# ControlPCB_2025-04-28.net
KiCad netlist of a schematic drawn in EAGLE
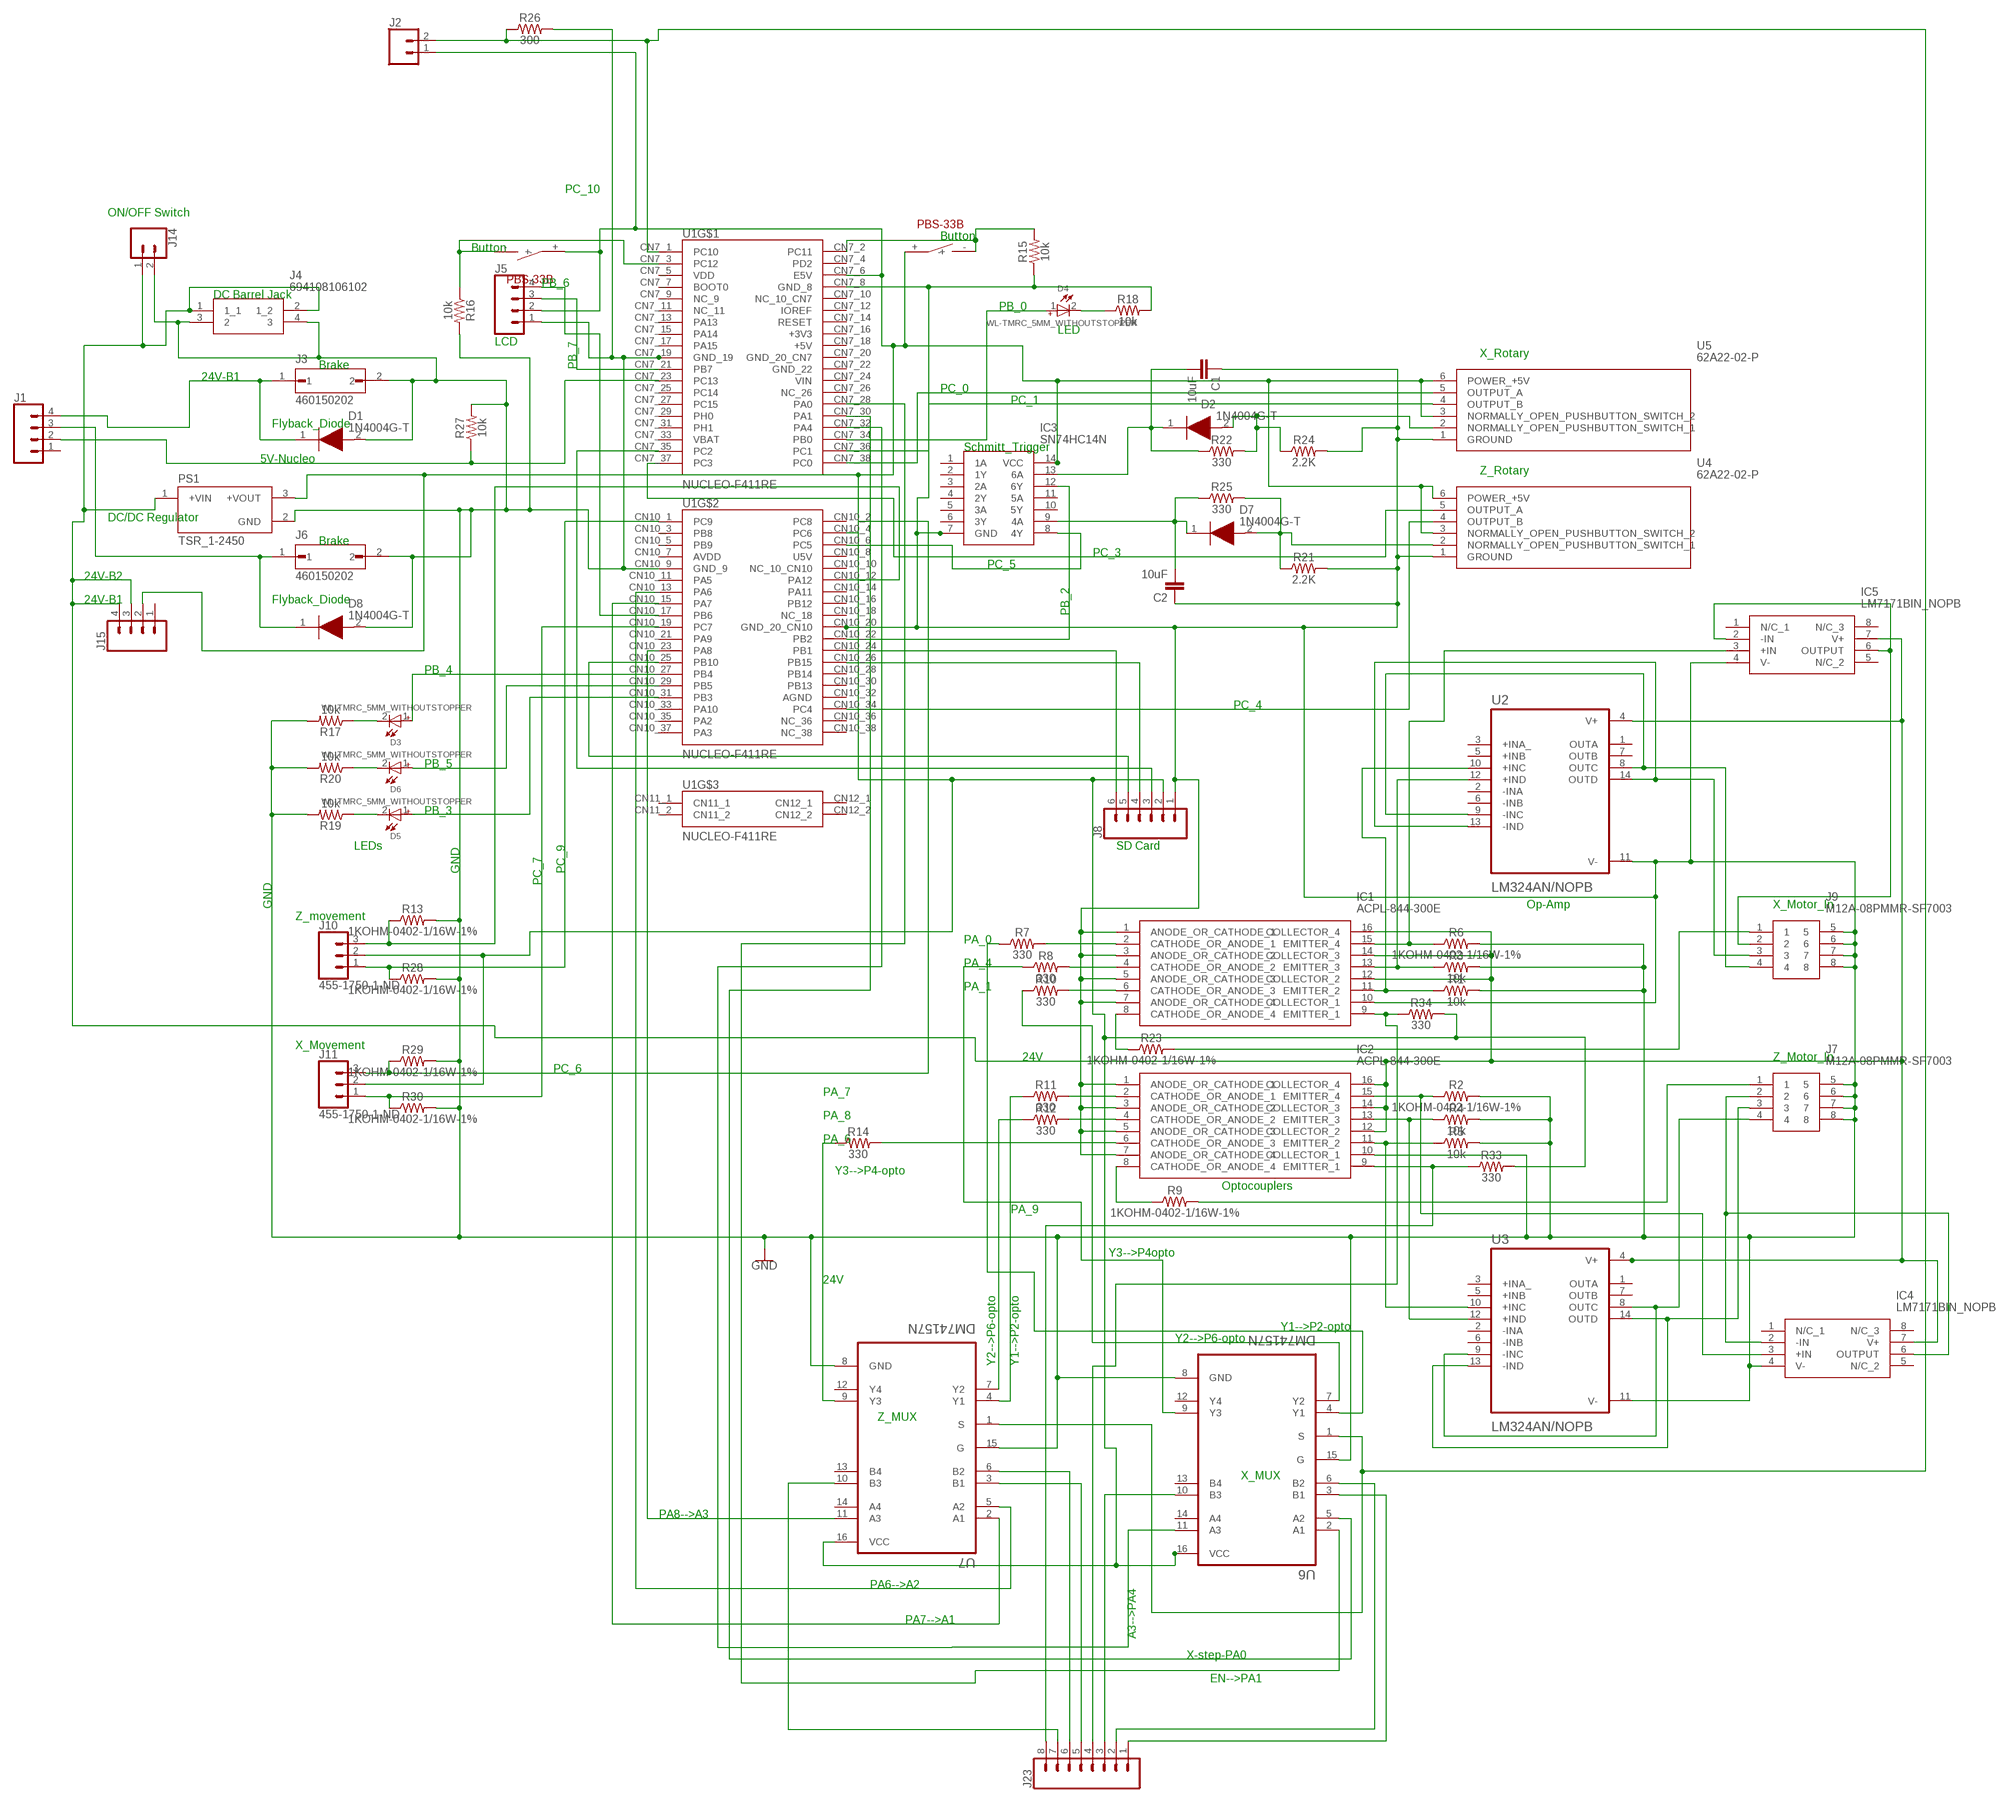
[diagram p0: schematic, sheet 1]

(export (version "E")
  (design (tool "Eeschema 10.0.6"))
  (components
    (comp (ref "C1")
      (value "10uF")
      (footprint "eagle-import:0603")
      (libsource (lib "eagle-import") (part "10UF-0603-6.3V-20%"))
    )
    (comp (ref "C2")
      (value "10uF")
      (footprint "eagle-import:0603")
      (libsource (lib "eagle-import") (part "10UF-0603-6.3V-20%"))
    )
    (comp (ref "D1")
      (value "1N4004G-T")
      (footprint "eagle-import:DIOAD1408W86L464D236")
      (fields (field (name "MOUSER_PART_NUMBER") "621-1N4004G-T"))
      (libsource (lib "eagle-import") (part "1N4004G-T"))
    )
    (comp (ref "D2")
      (value "1N4004G-T")
      (footprint "eagle-import:DIOAD1408W86L464D236")
      (fields (field (name "MOUSER_PART_NUMBER") "621-1N4004G-T"))
      (libsource (lib "eagle-import") (part "1N4004G-T"))
    )
    (comp (ref "D3")
      (value "WL-TMRC_5MM_WITHOUTSTOPPER")
      (footprint "eagle-import:WL-TMRC_5MM")
      (libsource (lib "eagle-import") (part "WL-TMRC_5MM_WITHOUTSTOPPER"))
    )
    (comp (ref "D4")
      (value "WL-TMRC_5MM_WITHOUTSTOPPER")
      (footprint "eagle-import:WL-TMRC_5MM")
      (libsource (lib "eagle-import") (part "WL-TMRC_5MM_WITHOUTSTOPPER"))
    )
    (comp (ref "D5")
      (value "WL-TMRC_5MM_WITHOUTSTOPPER")
      (footprint "eagle-import:WL-TMRC_5MM")
      (libsource (lib "eagle-import") (part "WL-TMRC_5MM_WITHOUTSTOPPER"))
    )
    (comp (ref "D6")
      (value "WL-TMRC_5MM_WITHOUTSTOPPER")
      (footprint "eagle-import:WL-TMRC_5MM")
      (libsource (lib "eagle-import") (part "WL-TMRC_5MM_WITHOUTSTOPPER"))
    )
    (comp (ref "D7")
      (value "1N4004G-T")
      (footprint "eagle-import:DIOAD1408W86L464D236")
      (fields (field (name "MOUSER_PART_NUMBER") "621-1N4004G-T"))
      (libsource (lib "eagle-import") (part "1N4004G-T"))
    )
    (comp (ref "D8")
      (value "1N4004G-T")
      (footprint "eagle-import:DIOAD1408W86L464D236")
      (fields (field (name "MOUSER_PART_NUMBER") "621-1N4004G-T"))
      (libsource (lib "eagle-import") (part "1N4004G-T"))
    )
    (comp (ref "IC1")
      (value "ACPL-844-300E")
      (footprint "eagle-import:DIP880W60P254L1984H450Q16N")
      (fields (field (name "MOUSER_PART_NUMBER") "630-ACPL-844-300E"))
      (libsource (lib "eagle-import") (part "ACPL-844-300E"))
    )
    (comp (ref "IC2")
      (value "ACPL-844-300E")
      (footprint "eagle-import:DIP880W60P254L1984H450Q16N")
      (fields (field (name "MOUSER_PART_NUMBER") "630-ACPL-844-300E"))
      (libsource (lib "eagle-import") (part "ACPL-844-300E"))
    )
    (comp (ref "IC3")
      (value "SN74HC14N")
      (footprint "eagle-import:DIP794W53P254L1930H508Q14N")
      (fields (field (name "MOUSER_PART_NUMBER") "595-SN74HC14N"))
      (libsource (lib "eagle-import") (part "SN74HC14N"))
    )
    (comp (ref "IC4")
      (value "LM7171BIN_NOPB")
      (footprint "eagle-import:DIP794W53P254L959H508Q8N")
      (fields
        (field (name "ARROW_PART_NUMBER") "LM7171BIN/NOPB")
        (field (name "MOUSER_PART_NUMBER") "926-LM7171BIN/NOPB")
      )
      (libsource (lib "eagle-import") (part "LM7171BIN_NOPB"))
    )
    (comp (ref "IC5")
      (value "LM7171BIN_NOPB")
      (footprint "eagle-import:DIP794W53P254L959H508Q8N")
      (fields
        (field (name "ARROW_PART_NUMBER") "LM7171BIN/NOPB")
        (field (name "MOUSER_PART_NUMBER") "926-LM7171BIN/NOPB")
      )
      (libsource (lib "eagle-import") (part "LM7171BIN_NOPB"))
    )
    (comp (ref "J1")
      (value "CONN_04PTH")
      (footprint "eagle-import:1X04")
      (libsource (lib "eagle-import") (part "CONN_04PTH"))
    )
    (comp (ref "J2")
      (value "CONN_02")
      (footprint "eagle-import:1X02")
      (libsource (lib "eagle-import") (part "CONN_02"))
    )
    (comp (ref "J3")
      (value "460150202")
      (footprint "eagle-import:MOLEX_460150202")
      (fields (field (name "MANUFACTURER") "Molex"))
      (libsource (lib "eagle-import") (part "460150202"))
    )
    (comp (ref "J4")
      (value "694108106102")
      (footprint "eagle-import:694108106102")
      (fields (field (name "MOUSER_PART_NUMBER") "710-694108106102"))
      (libsource (lib "eagle-import") (part "694108106102"))
    )
    (comp (ref "J5")
      (value "CONN_04LOCK")
      (footprint "eagle-import:1X04_LOCK")
      (libsource (lib "eagle-import") (part "CONN_04LOCK"))
    )
    (comp (ref "J6")
      (value "460150202")
      (footprint "eagle-import:MOLEX_460150202")
      (fields (field (name "MANUFACTURER") "Molex"))
      (libsource (lib "eagle-import") (part "460150202"))
    )
    (comp (ref "J7")
      (value "M12A-08PMMR-SF7003")
      (footprint "eagle-import:M12A08PMMRSF7003")
      (fields (field (name "MOUSER_PART_NUMBER") "523-M12A08PMMRSF7003"))
      (libsource (lib "eagle-import") (part "M12A-08PMMR-SF7003"))
    )
    (comp (ref "J8")
      (value "CONN_06SILK_FEMALE_PTH")
      (footprint "eagle-import:1X06")
      (libsource (lib "eagle-import") (part "CONN_06SILK_FEMALE_PTH"))
    )
    (comp (ref "J9")
      (value "M12A-08PMMR-SF7003")
      (footprint "eagle-import:M12A08PMMRSF7003")
      (fields (field (name "MOUSER_PART_NUMBER") "523-M12A08PMMRSF7003"))
      (libsource (lib "eagle-import") (part "M12A-08PMMR-SF7003"))
    )
    (comp (ref "J10")
      (value "455-1750-1-ND")
      (footprint "eagle-import:1X03")
      (libsource (lib "eagle-import") (part "CONN_03"))
    )
    (comp (ref "J11")
      (value "455-1750-1-ND")
      (footprint "eagle-import:1X03")
      (libsource (lib "eagle-import") (part "CONN_03"))
    )
    (comp (ref "J14")
      (value "CONN_02")
      (footprint "eagle-import:1X02")
      (libsource (lib "eagle-import") (part "CONN_02"))
    )
    (comp (ref "J15")
      (value "CONN_04PTH")
      (footprint "eagle-import:1X04")
      (libsource (lib "eagle-import") (part "CONN_04PTH"))
    )
    (comp (ref "J23")
      (value "CONN_08\"")
      (footprint "eagle-import:1X08")
      (libsource (lib "eagle-import") (part "CONN_08{dblquote}"))
    )
    (comp (ref "PS1")
      (value "TSR_1-2450")
      (footprint "eagle-import:CONV_TSR_1-2450")
      (fields (field (name "MANUFACTURER") "Traco Power"))
      (libsource (lib "eagle-import") (part "TSR_1-2450"))
    )
    (comp (ref "R1")
      (value "10k")
      (footprint "eagle-import:0402")
      (libsource (lib "eagle-import") (part "10KOHM-0402-1/16W-1%"))
    )
    (comp (ref "R2")
      (value "1KOHM-0402-1/16W-1%")
      (footprint "eagle-import:0402")
      (libsource (lib "eagle-import") (part "1KOHM-0402-1/16W-1%"))
    )
    (comp (ref "R3")
      (value "10k")
      (footprint "eagle-import:0402")
      (libsource (lib "eagle-import") (part "10KOHM-0402-1/16W-1%"))
    )
    (comp (ref "R4")
      (value "10k")
      (footprint "eagle-import:0402")
      (libsource (lib "eagle-import") (part "10KOHM-0402-1/16W-1%"))
    )
    (comp (ref "R5")
      (value "10k")
      (footprint "eagle-import:0402")
      (libsource (lib "eagle-import") (part "10KOHM-0402-1/16W-1%"))
    )
    (comp (ref "R6")
      (value "1KOHM-0402-1/16W-1%")
      (footprint "eagle-import:0402")
      (libsource (lib "eagle-import") (part "1KOHM-0402-1/16W-1%"))
    )
    (comp (ref "R7")
      (value "330")
      (footprint "eagle-import:0402")
      (libsource (lib "eagle-import") (part "330OHM-0402-1/16W-5%"))
    )
    (comp (ref "R8")
      (value "330")
      (footprint "eagle-import:0402")
      (libsource (lib "eagle-import") (part "330OHM-0402-1/16W-5%"))
    )
    (comp (ref "R9")
      (value "1KOHM-0402-1/16W-1%")
      (footprint "eagle-import:0402")
      (libsource (lib "eagle-import") (part "1KOHM-0402-1/16W-1%"))
    )
    (comp (ref "R10")
      (value "330")
      (footprint "eagle-import:0402")
      (libsource (lib "eagle-import") (part "330OHM-0402-1/16W-5%"))
    )
    (comp (ref "R11")
      (value "330")
      (footprint "eagle-import:0402")
      (libsource (lib "eagle-import") (part "330OHM-0402-1/16W-5%"))
    )
    (comp (ref "R12")
      (value "330")
      (footprint "eagle-import:0402")
      (libsource (lib "eagle-import") (part "330OHM-0402-1/16W-5%"))
    )
    (comp (ref "R13")
      (value "1KOHM-0402-1/16W-1%")
      (footprint "eagle-import:0402")
      (libsource (lib "eagle-import") (part "1KOHM-0402-1/16W-1%"))
    )
    (comp (ref "R14")
      (value "330")
      (footprint "eagle-import:0402")
      (libsource (lib "eagle-import") (part "330OHM-0402-1/16W-5%"))
    )
    (comp (ref "R15")
      (value "10k")
      (footprint "eagle-import:0402")
      (libsource (lib "eagle-import") (part "10KOHM-0402-1/16W-1%"))
    )
    (comp (ref "R16")
      (value "10k")
      (footprint "eagle-import:0402")
      (libsource (lib "eagle-import") (part "10KOHM-0402-1/16W-1%"))
    )
    (comp (ref "R17")
      (value "10k")
      (footprint "eagle-import:0402")
      (libsource (lib "eagle-import") (part "10KOHM-0402-1/16W-1%"))
    )
    (comp (ref "R18")
      (value "10k")
      (footprint "eagle-import:0402")
      (libsource (lib "eagle-import") (part "10KOHM-0402-1/16W-1%"))
    )
    (comp (ref "R19")
      (value "10k")
      (footprint "eagle-import:0402")
      (libsource (lib "eagle-import") (part "10KOHM-0402-1/16W-1%"))
    )
    (comp (ref "R20")
      (value "10k")
      (footprint "eagle-import:0402")
      (libsource (lib "eagle-import") (part "10KOHM-0402-1/16W-1%"))
    )
    (comp (ref "R21")
      (value "2.2K")
      (footprint "eagle-import:0402")
      (libsource (lib "eagle-import") (part "2.2KOHM-0402-1/16W-1%"))
    )
    (comp (ref "R22")
      (value "330")
      (footprint "eagle-import:0402")
      (libsource (lib "eagle-import") (part "330OHM-0402-1/16W-5%"))
    )
    (comp (ref "R23")
      (value "1KOHM-0402-1/16W-1%")
      (footprint "eagle-import:0402")
      (libsource (lib "eagle-import") (part "1KOHM-0402-1/16W-1%"))
    )
    (comp (ref "R24")
      (value "2.2K")
      (footprint "eagle-import:0402")
      (libsource (lib "eagle-import") (part "2.2KOHM-0402-1/16W-1%"))
    )
    (comp (ref "R25")
      (value "330")
      (footprint "eagle-import:0402")
      (libsource (lib "eagle-import") (part "330OHM-0402-1/16W-5%"))
    )
    (comp (ref "R26")
      (value "300")
      (footprint "eagle-import:0603")
      (libsource (lib "eagle-import") (part "300OHM-0603-1/10W-1%"))
    )
    (comp (ref "R27")
      (value "10k")
      (footprint "eagle-import:0402")
      (libsource (lib "eagle-import") (part "10KOHM-0402-1/16W-1%"))
    )
    (comp (ref "R28")
      (value "1KOHM-0402-1/16W-1%")
      (footprint "eagle-import:0402")
      (libsource (lib "eagle-import") (part "1KOHM-0402-1/16W-1%"))
    )
    (comp (ref "R29")
      (value "1KOHM-0402-1/16W-1%")
      (footprint "eagle-import:0402")
      (libsource (lib "eagle-import") (part "1KOHM-0402-1/16W-1%"))
    )
    (comp (ref "R30")
      (value "1KOHM-0402-1/16W-1%")
      (footprint "eagle-import:0402")
      (libsource (lib "eagle-import") (part "1KOHM-0402-1/16W-1%"))
    )
    (comp (ref "R33")
      (value "330")
      (footprint "eagle-import:0402")
      (libsource (lib "eagle-import") (part "330OHM-0402-1/16W-5%"))
    )
    (comp (ref "R34")
      (value "330")
      (footprint "eagle-import:0402")
      (libsource (lib "eagle-import") (part "330OHM-0402-1/16W-5%"))
    )
    (comp (ref "U$1")
      (value "PBS-33B")
      (footprint "eagle-import:PBS-33B")
      (libsource (lib "eagle-import") (part "PBS-33B"))
    )
    (comp (ref "U$2")
      (value "PBS-33B")
      (footprint "eagle-import:PBS-33B")
      (libsource (lib "eagle-import") (part "PBS-33B"))
    )
    (comp (ref "U1")
      (value "NUCLEO-F411RE")
      (footprint "eagle-import:BOARD_NUCLEO-F411RE")
      (fields (field (name "DIGIKEY_PART_NUMBER") "497-14711-ND") (field (name "MF") "STMicroelectronics"))
      (libsource (lib "eagle-import") (part "NUCLEO-F411RE"))
    )
    (comp (ref "U2")
      (value "LM324AN/NOPB")
      (footprint "eagle-import:DIP794W45P254L1969H508Q14")
      (libsource (lib "eagle-import") (part "LM324AN/NOPB"))
    )
    (comp (ref "U3")
      (value "LM324AN/NOPB")
      (footprint "eagle-import:DIP794W45P254L1969H508Q14")
      (libsource (lib "eagle-import") (part "LM324AN/NOPB"))
    )
    (comp (ref "U4")
      (value "62A22-02-P")
      (footprint "eagle-import:62A2202P")
      (fields (field (name "MOUSER_PART_NUMBER") "706-62A22-02-P"))
      (libsource (lib "eagle-import") (part "62A22-02-P"))
    )
    (comp (ref "U5")
      (value "62A22-02-P")
      (footprint "eagle-import:62A2202P")
      (fields (field (name "MOUSER_PART_NUMBER") "706-62A22-02-P"))
      (libsource (lib "eagle-import") (part "62A22-02-P"))
    )
    (comp (ref "U6")
      (value "DM74157N")
      (footprint "eagle-import:DIP794W45P254L1918H533Q16")
      (fields (field (name "MF") "ON Semiconductor"))
      (libsource (lib "eagle-import") (part "DM74157N"))
    )
    (comp (ref "U7")
      (value "DM74157N")
      (footprint "eagle-import:DIP794W45P254L1918H533Q16")
      (fields (field (name "MF") "ON Semiconductor"))
      (libsource (lib "eagle-import") (part "DM74157N"))
    )
  )
  (nets
    (net (code "1") (name "/+3V3") (class "Default")
      (node (ref "U1") (pin "CN7_16") (pinfunction "+3V3_CN7_16") (pintype "power_in"))
    )
    (net (code "2") (name "/+5V") (class "Default")
      (node (ref "U1") (pin "CN7_18") (pinfunction "+5V_CN7_18") (pintype "power_in"))
    )
    (net (code "3") (name "/AGND") (class "Default")
      (node (ref "U1") (pin "CN10_32") (pinfunction "AGND_CN10_32") (pintype "power_in"))
    )
    (net (code "4") (name "/AVDD") (class "Default")
      (node (ref "U1") (pin "CN10_7") (pinfunction "AVDD_CN10_7") (pintype "power_in"))
    )
    (net (code "5") (name "/GND_20_CN7") (class "Default")
      (node (ref "U1") (pin "CN7_20") (pinfunction "GND_20_CN7_CN7_20") (pintype "power_in"))
    )
    (net (code "6") (name "/GND_22") (class "Default")
      (node (ref "U1") (pin "CN7_22") (pinfunction "GND_22_CN7_22") (pintype "power_in"))
    )
    (net (code "7") (name "/U5V") (class "Default")
      (node (ref "U1") (pin "CN10_8") (pinfunction "U5V_CN10_8") (pintype "power_in"))
    )
    (net (code "8") (name "/VBAT") (class "Default")
      (node (ref "U1") (pin "CN7_33") (pinfunction "VBAT_CN7_33") (pintype "power_in"))
    )
    (net (code "9") (name "/VDD") (class "Default")
      (node (ref "U1") (pin "CN7_5") (pinfunction "VDD_CN7_5") (pintype "power_in"))
    )
    (net (code "10") (name "GND") (class "Default")
      (node (ref "C1") (pin "1") (pinfunction "1_1") (pintype "passive"))
      (node (ref "C2") (pin "1") (pinfunction "1_1") (pintype "passive"))
      (node (ref "D1") (pin "2") (pinfunction "A_2") (pintype "bidirectional"))
      (node (ref "D8") (pin "2") (pinfunction "A_2") (pintype "bidirectional"))
      (node (ref "IC1") (pin "1") (pinfunction "ANODE_OR_CATHODE_1_1") (pintype "bidirectional"))
      (node (ref "IC1") (pin "10") (pinfunction "COLLECTOR_1_10") (pintype "bidirectional"))
      (node (ref "IC1") (pin "3") (pinfunction "ANODE_OR_CATHODE_2_3") (pintype "bidirectional"))
      (node (ref "IC1") (pin "5") (pinfunction "ANODE_OR_CATHODE_3_5") (pintype "bidirectional"))
      (node (ref "IC1") (pin "7") (pinfunction "ANODE_OR_CATHODE_4_7") (pintype "bidirectional"))
      (node (ref "IC2") (pin "1") (pinfunction "ANODE_OR_CATHODE_1_1") (pintype "bidirectional"))
      (node (ref "IC2") (pin "10") (pinfunction "COLLECTOR_1_10") (pintype "bidirectional"))
      (node (ref "IC2") (pin "3") (pinfunction "ANODE_OR_CATHODE_2_3") (pintype "bidirectional"))
      (node (ref "IC2") (pin "5") (pinfunction "ANODE_OR_CATHODE_3_5") (pintype "bidirectional"))
      (node (ref "IC2") (pin "7") (pinfunction "ANODE_OR_CATHODE_4_7") (pintype "bidirectional"))
      (node (ref "IC3") (pin "7") (pinfunction "GND_7") (pintype "bidirectional"))
      (node (ref "IC4") (pin "4") (pinfunction "V-_4") (pintype "bidirectional"))
      (node (ref "IC5") (pin "4") (pinfunction "V-_4") (pintype "bidirectional"))
      (node (ref "J14") (pin "2") (pinfunction "2_2") (pintype "passive"))
      (node (ref "J3") (pin "2") (pinfunction "2_2") (pintype "passive"))
      (node (ref "J4") (pin "3") (pinfunction "2_3") (pintype "bidirectional"))
      (node (ref "J4") (pin "4") (pinfunction "3_4") (pintype "bidirectional"))
      (node (ref "J5") (pin "1") (pinfunction "1_1") (pintype "passive"))
      (node (ref "J6") (pin "2") (pinfunction "2_2") (pintype "passive"))
      (node (ref "J7") (pin "5") (pinfunction "5_5") (pintype "bidirectional"))
      (node (ref "J7") (pin "6") (pinfunction "6_6") (pintype "bidirectional"))
      (node (ref "J7") (pin "7") (pinfunction "7_7") (pintype "bidirectional"))
      (node (ref "J7") (pin "8") (pinfunction "8_8") (pintype "bidirectional"))
      (node (ref "J8") (pin "1") (pinfunction "1_1") (pintype "passive"))
      (node (ref "J9") (pin "5") (pinfunction "5_5") (pintype "bidirectional"))
      (node (ref "J9") (pin "6") (pinfunction "6_6") (pintype "bidirectional"))
      (node (ref "J9") (pin "7") (pinfunction "7_7") (pintype "bidirectional"))
      (node (ref "J9") (pin "8") (pinfunction "8_8") (pintype "bidirectional"))
      (node (ref "PS1") (pin "2") (pinfunction "GND_2") (pintype "power_in"))
      (node (ref "R1") (pin "2") (pinfunction "2_2") (pintype "passive"))
      (node (ref "R13") (pin "2") (pinfunction "2_2") (pintype "passive"))
      (node (ref "R15") (pin "1") (pinfunction "1_1") (pintype "passive"))
      (node (ref "R16") (pin "2") (pinfunction "2_2") (pintype "passive"))
      (node (ref "R17") (pin "2") (pinfunction "2_2") (pintype "passive"))
      (node (ref "R18") (pin "2") (pinfunction "2_2") (pintype "passive"))
      (node (ref "R19") (pin "2") (pinfunction "2_2") (pintype "passive"))
      (node (ref "R2") (pin "2") (pinfunction "2_2") (pintype "passive"))
      (node (ref "R20") (pin "2") (pinfunction "2_2") (pintype "passive"))
      (node (ref "R21") (pin "2") (pinfunction "2_2") (pintype "passive"))
      (node (ref "R24") (pin "2") (pinfunction "2_2") (pintype "passive"))
      (node (ref "R26") (pin "2") (pinfunction "2_2") (pintype "passive"))
      (node (ref "R27") (pin "2") (pinfunction "2_2") (pintype "passive"))
      (node (ref "R28") (pin "2") (pinfunction "2_2") (pintype "passive"))
      (node (ref "R29") (pin "2") (pinfunction "2_2") (pintype "passive"))
      (node (ref "R3") (pin "2") (pinfunction "2_2") (pintype "passive"))
      (node (ref "R30") (pin "2") (pinfunction "2_2") (pintype "passive"))
      (node (ref "R4") (pin "2") (pinfunction "2_2") (pintype "passive"))
      (node (ref "R5") (pin "2") (pinfunction "2_2") (pintype "passive"))
      (node (ref "R6") (pin "2") (pinfunction "2_2") (pintype "passive"))
      (node (ref "U1") (pin "CN10_20") (pinfunction "GND_20_CN10_CN10_20") (pintype "power_in"))
      (node (ref "U1") (pin "CN10_9") (pinfunction "GND_9_CN10_9") (pintype "power_in"))
      (node (ref "U1") (pin "CN7_19") (pinfunction "GND_19_CN7_19") (pintype "power_in"))
      (node (ref "U1") (pin "CN7_8") (pinfunction "GND_8_CN7_8") (pintype "power_in"))
      (node (ref "U2") (pin "11") (pinfunction "V-_11") (pintype "power_in"))
      (node (ref "U3") (pin "11") (pinfunction "V-_11") (pintype "power_in"))
      (node (ref "U4") (pin "1") (pinfunction "GROUND_1") (pintype "bidirectional"))
      (node (ref "U5") (pin "1") (pinfunction "GROUND_1") (pintype "bidirectional"))
      (node (ref "U6") (pin "15") (pinfunction "G_15") (pintype "bidirectional"))
      (node (ref "U6") (pin "8") (pinfunction "GND_8") (pintype "power_in"))
      (node (ref "U7") (pin "15") (pinfunction "G_15") (pintype "bidirectional"))
      (node (ref "U7") (pin "8") (pinfunction "GND_8") (pintype "power_in"))
    )
    (net (code "11") (name "Net-(D1-K)") (class "Default")
      (node (ref "D1") (pin "1") (pinfunction "K_1") (pintype "bidirectional"))
      (node (ref "J1") (pin "4") (pinfunction "4_4") (pintype "passive"))
      (node (ref "J3") (pin "1") (pinfunction "1_1") (pintype "passive"))
    )
    (net (code "12") (name "Net-(D2-A)") (class "Default")
      (node (ref "D2") (pin "2") (pinfunction "A_2") (pintype "bidirectional"))
      (node (ref "R22") (pin "2") (pinfunction "2_2") (pintype "passive"))
      (node (ref "R24") (pin "1") (pinfunction "1_1") (pintype "passive"))
      (node (ref "U5") (pin "2") (pinfunction "NORMALLY_OPEN_PUSHBUTTON_SWITCH_1_2") (pintype "bidirectional"))
    )
    (net (code "13") (name "Net-(D2-K)") (class "Default")
      (node (ref "C1") (pin "2") (pinfunction "2_2") (pintype "passive"))
      (node (ref "D2") (pin "1") (pinfunction "K_1") (pintype "bidirectional"))
      (node (ref "IC3") (pin "13") (pinfunction "6A_13") (pintype "bidirectional"))
      (node (ref "R22") (pin "1") (pinfunction "1_1") (pintype "passive"))
    )
    (net (code "14") (name "Net-(D3-+)") (class "Default")
      (node (ref "D3") (pin "1") (pinfunction "+_1") (pintype "passive"))
      (node (ref "U1") (pin "CN10_27") (pinfunction "PB4_CN10_27") (pintype "bidirectional"))
    )
    (net (code "15") (name "Net-(D3--)") (class "Default")
      (node (ref "D3") (pin "2") (pinfunction "-_2") (pintype "passive"))
      (node (ref "R17") (pin "1") (pinfunction "1_1") (pintype "passive"))
    )
    (net (code "16") (name "Net-(D4-+)") (class "Default")
      (node (ref "D4") (pin "1") (pinfunction "+_1") (pintype "passive"))
      (node (ref "U1") (pin "CN7_34") (pinfunction "PB0_CN7_34") (pintype "bidirectional"))
    )
    (net (code "17") (name "Net-(D4--)") (class "Default")
      (node (ref "D4") (pin "2") (pinfunction "-_2") (pintype "passive"))
      (node (ref "R18") (pin "1") (pinfunction "1_1") (pintype "passive"))
    )
    (net (code "18") (name "Net-(D5-+)") (class "Default")
      (node (ref "D5") (pin "1") (pinfunction "+_1") (pintype "passive"))
      (node (ref "U1") (pin "CN10_31") (pinfunction "PB3_CN10_31") (pintype "bidirectional"))
    )
    (net (code "19") (name "Net-(D5--)") (class "Default")
      (node (ref "D5") (pin "2") (pinfunction "-_2") (pintype "passive"))
      (node (ref "R19") (pin "1") (pinfunction "1_1") (pintype "passive"))
    )
    (net (code "20") (name "Net-(D6-+)") (class "Default")
      (node (ref "D6") (pin "1") (pinfunction "+_1") (pintype "passive"))
      (node (ref "U1") (pin "CN10_29") (pinfunction "PB5_CN10_29") (pintype "bidirectional"))
    )
    (net (code "21") (name "Net-(D6--)") (class "Default")
      (node (ref "D6") (pin "2") (pinfunction "-_2") (pintype "passive"))
      (node (ref "R20") (pin "1") (pinfunction "1_1") (pintype "passive"))
    )
    (net (code "22") (name "Net-(D7-A)") (class "Default")
      (node (ref "D7") (pin "2") (pinfunction "A_2") (pintype "bidirectional"))
      (node (ref "R21") (pin "1") (pinfunction "1_1") (pintype "passive"))
      (node (ref "R25") (pin "2") (pinfunction "2_2") (pintype "passive"))
      (node (ref "U4") (pin "2") (pinfunction "NORMALLY_OPEN_PUSHBUTTON_SWITCH_1_2") (pintype "bidirectional"))
    )
    (net (code "23") (name "Net-(D7-K)") (class "Default")
      (node (ref "C2") (pin "2") (pinfunction "2_2") (pintype "passive"))
      (node (ref "D7") (pin "1") (pinfunction "K_1") (pintype "bidirectional"))
      (node (ref "IC3") (pin "9") (pinfunction "4A_9") (pintype "bidirectional"))
      (node (ref "R25") (pin "1") (pinfunction "1_1") (pintype "passive"))
    )
    (net (code "24") (name "Net-(D8-K)") (class "Default")
      (node (ref "D8") (pin "1") (pinfunction "K_1") (pintype "bidirectional"))
      (node (ref "J1") (pin "3") (pinfunction "3_3") (pintype "passive"))
      (node (ref "J6") (pin "1") (pinfunction "1_1") (pintype "passive"))
    )
    (net (code "25") (name "Net-(IC1-CATHODE_OR_ANODE_1)") (class "Default")
      (node (ref "IC1") (pin "2") (pinfunction "CATHODE_OR_ANODE_1_2") (pintype "bidirectional"))
      (node (ref "R7") (pin "2") (pinfunction "2_2") (pintype "passive"))
    )
    (net (code "26") (name "Net-(IC1-CATHODE_OR_ANODE_2)") (class "Default")
      (node (ref "IC1") (pin "4") (pinfunction "CATHODE_OR_ANODE_2_4") (pintype "bidirectional"))
      (node (ref "R8") (pin "2") (pinfunction "2_2") (pintype "passive"))
    )
    (net (code "27") (name "Net-(IC1-CATHODE_OR_ANODE_3)") (class "Default")
      (node (ref "IC1") (pin "6") (pinfunction "CATHODE_OR_ANODE_3_6") (pintype "bidirectional"))
      (node (ref "R10") (pin "2") (pinfunction "2_2") (pintype "passive"))
    )
    (net (code "28") (name "Net-(IC1-CATHODE_OR_ANODE_4)") (class "Default")
      (node (ref "IC1") (pin "8") (pinfunction "CATHODE_OR_ANODE_4_8") (pintype "bidirectional"))
      (node (ref "R23") (pin "1") (pinfunction "1_1") (pintype "passive"))
    )
    (net (code "29") (name "Net-(IC1-COLLECTOR_2)") (class "Default")
      (node (ref "IC1") (pin "12") (pinfunction "COLLECTOR_2_12") (pintype "bidirectional"))
      (node (ref "IC1") (pin "14") (pinfunction "COLLECTOR_3_14") (pintype "bidirectional"))
      (node (ref "IC1") (pin "16") (pinfunction "COLLECTOR_4_16") (pintype "bidirectional"))
      (node (ref "IC2") (pin "12") (pinfunction "COLLECTOR_2_12") (pintype "bidirectional"))
      (node (ref "IC2") (pin "14") (pinfunction "COLLECTOR_3_14") (pintype "bidirectional"))
      (node (ref "IC2") (pin "16") (pinfunction "COLLECTOR_4_16") (pintype "bidirectional"))
      (node (ref "IC4") (pin "7") (pinfunction "V+_7") (pintype "bidirectional"))
      (node (ref "IC5") (pin "7") (pinfunction "V+_7") (pintype "bidirectional"))
      (node (ref "J14") (pin "1") (pinfunction "1_1") (pintype "passive"))
      (node (ref "J15") (pin "3") (pinfunction "3_3") (pintype "passive"))
      (node (ref "J15") (pin "4") (pinfunction "4_4") (pintype "passive"))
      (node (ref "J4") (pin "1") (pinfunction "1_1_1") (pintype "bidirectional"))
      (node (ref "J4") (pin "2") (pinfunction "1_2_2") (pintype "bidirectional"))
      (node (ref "PS1") (pin "1") (pinfunction "+VIN_1") (pintype "input"))
      (node (ref "U2") (pin "4") (pinfunction "V+_4") (pintype "power_in"))
      (node (ref "U3") (pin "4") (pinfunction "V+_4") (pintype "power_in"))
    )
    (net (code "30") (name "Net-(IC1-EMITTER_1)") (class "Default")
      (node (ref "IC1") (pin "9") (pinfunction "EMITTER_1_9") (pintype "bidirectional"))
      (node (ref "J23") (pin "4") (pinfunction "4_4") (pintype "passive"))
      (node (ref "R34") (pin "1") (pinfunction "1_1") (pintype "passive"))
    )
    (net (code "31") (name "Net-(IC1-EMITTER_2)") (class "Default")
      (node (ref "IC1") (pin "11") (pinfunction "EMITTER_2_11") (pintype "bidirectional"))
      (node (ref "R1") (pin "1") (pinfunction "1_1") (pintype "passive"))
      (node (ref "U2") (pin "10") (pinfunction "+INC_10") (pintype "input"))
    )
    (net (code "32") (name "Net-(IC1-EMITTER_3)") (class "Default")
      (node (ref "IC1") (pin "13") (pinfunction "EMITTER_3_13") (pintype "bidirectional"))
      (node (ref "R3") (pin "1") (pinfunction "1_1") (pintype "passive"))
      (node (ref "U2") (pin "12") (pinfunction "+IND_12") (pintype "input"))
    )
    (net (code "33") (name "Net-(IC1-EMITTER_4)") (class "Default")
      (node (ref "IC1") (pin "15") (pinfunction "EMITTER_4_15") (pintype "bidirectional"))
      (node (ref "IC5") (pin "3") (pinfunction "+IN_3") (pintype "bidirectional"))
      (node (ref "R6") (pin "1") (pinfunction "1_1") (pintype "passive"))
    )
    (net (code "34") (name "Net-(IC2-CATHODE_OR_ANODE_1)") (class "Default")
      (node (ref "IC2") (pin "2") (pinfunction "CATHODE_OR_ANODE_1_2") (pintype "bidirectional"))
      (node (ref "R11") (pin "2") (pinfunction "2_2") (pintype "passive"))
    )
    (net (code "35") (name "Net-(IC2-CATHODE_OR_ANODE_2)") (class "Default")
      (node (ref "IC2") (pin "4") (pinfunction "CATHODE_OR_ANODE_2_4") (pintype "bidirectional"))
      (node (ref "R12") (pin "2") (pinfunction "2_2") (pintype "passive"))
    )
    (net (code "36") (name "Net-(IC2-CATHODE_OR_ANODE_3)") (class "Default")
      (node (ref "IC2") (pin "6") (pinfunction "CATHODE_OR_ANODE_3_6") (pintype "bidirectional"))
      (node (ref "R14") (pin "2") (pinfunction "2_2") (pintype "passive"))
    )
    (net (code "37") (name "Net-(IC2-CATHODE_OR_ANODE_4)") (class "Default")
      (node (ref "IC2") (pin "8") (pinfunction "CATHODE_OR_ANODE_4_8") (pintype "bidirectional"))
      (node (ref "R9") (pin "1") (pinfunction "1_1") (pintype "passive"))
    )
    (net (code "38") (name "Net-(IC2-EMITTER_1)") (class "Default")
      (node (ref "IC2") (pin "9") (pinfunction "EMITTER_1_9") (pintype "bidirectional"))
      (node (ref "J23") (pin "8") (pinfunction "8_8") (pintype "passive"))
      (node (ref "R33") (pin "1") (pinfunction "1_1") (pintype "passive"))
    )
    (net (code "39") (name "Net-(IC2-EMITTER_2)") (class "Default")
      (node (ref "IC2") (pin "11") (pinfunction "EMITTER_2_11") (pintype "bidirectional"))
      (node (ref "R5") (pin "1") (pinfunction "1_1") (pintype "passive"))
      (node (ref "U3") (pin "10") (pinfunction "+INC_10") (pintype "input"))
    )
    (net (code "40") (name "Net-(IC2-EMITTER_3)") (class "Default")
      (node (ref "IC2") (pin "13") (pinfunction "EMITTER_3_13") (pintype "bidirectional"))
      (node (ref "R4") (pin "1") (pinfunction "1_1") (pintype "passive"))
      (node (ref "U3") (pin "12") (pinfunction "+IND_12") (pintype "input"))
    )
    (net (code "41") (name "Net-(IC2-EMITTER_4)") (class "Default")
      (node (ref "IC2") (pin "15") (pinfunction "EMITTER_4_15") (pintype "bidirectional"))
      (node (ref "IC4") (pin "3") (pinfunction "+IN_3") (pintype "bidirectional"))
      (node (ref "R2") (pin "1") (pinfunction "1_1") (pintype "passive"))
    )
    (net (code "42") (name "Net-(IC3-4Y)") (class "Default")
      (node (ref "IC3") (pin "8") (pinfunction "4Y_8") (pintype "bidirectional"))
      (node (ref "U1") (pin "CN10_6") (pinfunction "PC5_CN10_6") (pintype "bidirectional"))
    )
    (net (code "43") (name "Net-(IC3-6Y)") (class "Default")
      (node (ref "IC3") (pin "12") (pinfunction "6Y_12") (pintype "bidirectional"))
      (node (ref "U1") (pin "CN10_22") (pinfunction "PB2_CN10_22") (pintype "bidirectional"))
    )
    (net (code "44") (name "Net-(IC3-VCC)") (class "Default")
      (node (ref "IC3") (pin "14") (pinfunction "VCC_14") (pintype "bidirectional"))
      (node (ref "J10") (pin "2") (pinfunction "2_2") (pintype "passive"))
      (node (ref "J11") (pin "2") (pinfunction "2_2") (pintype "passive"))
      (node (ref "J15") (pin "2") (pinfunction "2_2") (pintype "passive"))
      (node (ref "J2") (pin "1") (pinfunction "1_1") (pintype "passive"))
      (node (ref "J5") (pin "2") (pinfunction "2_2") (pintype "passive"))
      (node (ref "J8") (pin "2") (pinfunction "2_2") (pintype "passive"))
      (node (ref "PS1") (pin "3") (pinfunction "+VOUT_3") (pintype "output"))
      (node (ref "R33") (pin "2") (pinfunction "2_2") (pintype "passive"))
      (node (ref "R34") (pin "2") (pinfunction "2_2") (pintype "passive"))
      (node (ref "U$1") (pin "+") (pinfunction "+_+") (pintype "bidirectional"))
      (node (ref "U$2") (pin "+") (pinfunction "+_+") (pintype "bidirectional"))
      (node (ref "U1") (pin "CN7_6") (pinfunction "E5V_CN7_6") (pintype "power_in"))
      (node (ref "U4") (pin "3") (pinfunction "NORMALLY_OPEN_PUSHBUTTON_SWITCH_2_3") (pintype "bidirectional"))
      (node (ref "U4") (pin "6") (pinfunction "POWER_+5V_6") (pintype "bidirectional"))
      (node (ref "U5") (pin "3") (pinfunction "NORMALLY_OPEN_PUSHBUTTON_SWITCH_2_3") (pintype "bidirectional"))
      (node (ref "U5") (pin "6") (pinfunction "POWER_+5V_6") (pintype "bidirectional"))
      (node (ref "U6") (pin "16") (pinfunction "VCC_16") (pintype "power_in"))
      (node (ref "U7") (pin "16") (pinfunction "VCC_16") (pintype "power_in"))
    )
    (net (code "45") (name "Net-(IC4--IN)") (class "Default")
      (node (ref "IC4") (pin "2") (pinfunction "-IN_2") (pintype "bidirectional"))
      (node (ref "IC4") (pin "6") (pinfunction "OUTPUT_6") (pintype "bidirectional"))
      (node (ref "J7") (pin "2") (pinfunction "2_2") (pintype "bidirectional"))
    )
    (net (code "46") (name "Net-(IC5--IN)") (class "Default")
      (node (ref "IC5") (pin "2") (pinfunction "-IN_2") (pintype "bidirectional"))
      (node (ref "IC5") (pin "6") (pinfunction "OUTPUT_6") (pintype "bidirectional"))
      (node (ref "J9") (pin "2") (pinfunction "2_2") (pintype "bidirectional"))
    )
    (net (code "47") (name "Net-(J7-Pad1)") (class "Default")
      (node (ref "J7") (pin "1") (pinfunction "1_1") (pintype "bidirectional"))
      (node (ref "R9") (pin "2") (pinfunction "2_2") (pintype "passive"))
    )
    (net (code "48") (name "Net-(J9-Pad1)") (class "Default")
      (node (ref "J9") (pin "1") (pinfunction "1_1") (pintype "bidirectional"))
      (node (ref "R23") (pin "2") (pinfunction "2_2") (pintype "passive"))
    )
    (net (code "49") (name "Net-(U1A-PA0)") (class "Default")
      (node (ref "U1") (pin "CN7_28") (pinfunction "PA0_CN7_28") (pintype "bidirectional"))
      (node (ref "U6") (pin "2") (pinfunction "A1_2") (pintype "bidirectional"))
    )
    (net (code "50") (name "Net-(U1A-PA1)") (class "Default")
      (node (ref "U1") (pin "CN7_30") (pinfunction "PA1_CN7_30") (pintype "bidirectional"))
      (node (ref "U6") (pin "5") (pinfunction "A2_5") (pintype "bidirectional"))
    )
    (net (code "51") (name "Net-(U1A-PA4)") (class "Default")
      (node (ref "U1") (pin "CN7_32") (pinfunction "PA4_CN7_32") (pintype "bidirectional"))
      (node (ref "U6") (pin "11") (pinfunction "A3_11") (pintype "bidirectional"))
    )
    (net (code "52") (name "Net-(U1A-PB7)") (class "Default")
      (node (ref "J5") (pin "3") (pinfunction "3_3") (pintype "passive"))
      (node (ref "U1") (pin "CN7_21") (pinfunction "PB7_CN7_21") (pintype "bidirectional"))
    )
    (net (code "53") (name "Net-(U1A-PC0)") (class "Default")
      (node (ref "U1") (pin "CN7_38") (pinfunction "PC0_CN7_38") (pintype "bidirectional"))
      (node (ref "U5") (pin "5") (pinfunction "OUTPUT_A_5") (pintype "bidirectional"))
    )
    (net (code "54") (name "Net-(U1A-PC1)") (class "Default")
      (node (ref "U1") (pin "CN7_36") (pinfunction "PC1_CN7_36") (pintype "bidirectional"))
      (node (ref "U5") (pin "4") (pinfunction "OUTPUT_B_4") (pintype "bidirectional"))
    )
    (net (code "55") (name "Net-(U1A-PC2)") (class "Default")
      (node (ref "J8") (pin "3") (pinfunction "3_3") (pintype "passive"))
      (node (ref "U1") (pin "CN7_35") (pinfunction "PC2_CN7_35") (pintype "bidirectional"))
    )
    (net (code "56") (name "Net-(U1A-PC3)") (class "Default")
      (node (ref "U1") (pin "CN7_37") (pinfunction "PC3_CN7_37") (pintype "bidirectional"))
      (node (ref "U4") (pin "5") (pinfunction "OUTPUT_A_5") (pintype "bidirectional"))
    )
    (net (code "57") (name "Net-(U1A-PC10)") (class "Default")
      (node (ref "J2") (pin "2") (pinfunction "2_2") (pintype "passive"))
      (node (ref "R26") (pin "1") (pinfunction "1_1") (pintype "passive"))
      (node (ref "U1") (pin "CN7_1") (pinfunction "PC10_CN7_1") (pintype "bidirectional"))
      (node (ref "U6") (pin "1") (pinfunction "S_1") (pintype "bidirectional"))
      (node (ref "U7") (pin "1") (pinfunction "S_1") (pintype "bidirectional"))
    )
    (net (code "58") (name "Net-(U1A-PC11)") (class "Default")
      (node (ref "R15") (pin "2") (pinfunction "2_2") (pintype "passive"))
      (node (ref "U$1") (pin "-") (pinfunction "-_-") (pintype "bidirectional"))
      (node (ref "U1") (pin "CN7_2") (pinfunction "PC11_CN7_2") (pintype "bidirectional"))
    )
    (net (code "59") (name "Net-(U1A-PC12)") (class "Default")
      (node (ref "R16") (pin "1") (pinfunction "1_1") (pintype "passive"))
      (node (ref "U$2") (pin "-") (pinfunction "-_-") (pintype "bidirectional"))
      (node (ref "U1") (pin "CN7_3") (pinfunction "PC12_CN7_3") (pintype "bidirectional"))
    )
    (net (code "60") (name "Net-(U1A-PC13)") (class "Default")
      (node (ref "J1") (pin "2") (pinfunction "2_2") (pintype "passive"))
      (node (ref "R27") (pin "1") (pinfunction "1_1") (pintype "passive"))
      (node (ref "U1") (pin "CN7_23") (pinfunction "PC13_CN7_23") (pintype "bidirectional"))
    )
    (net (code "61") (name "Net-(U1B-PA6)") (class "Default")
      (node (ref "U1") (pin "CN10_13") (pinfunction "PA6_CN10_13") (pintype "bidirectional"))
      (node (ref "U7") (pin "5") (pinfunction "A2_5") (pintype "bidirectional"))
    )
    (net (code "62") (name "Net-(U1B-PA7)") (class "Default")
      (node (ref "U1") (pin "CN10_15") (pinfunction "PA7_CN10_15") (pintype "bidirectional"))
      (node (ref "U7") (pin "2") (pinfunction "A1_2") (pintype "bidirectional"))
    )
    (net (code "63") (name "Net-(U1B-PA8)") (class "Default")
      (node (ref "U1") (pin "CN10_23") (pinfunction "PA8_CN10_23") (pintype "bidirectional"))
      (node (ref "U7") (pin "11") (pinfunction "A3_11") (pintype "bidirectional"))
    )
    (net (code "64") (name "Net-(U1B-PA12)") (class "Default")
      (node (ref "J10") (pin "3") (pinfunction "3_3") (pintype "passive"))
      (node (ref "R13") (pin "1") (pinfunction "1_1") (pintype "passive"))
      (node (ref "U1") (pin "CN10_12") (pinfunction "PA12_CN10_12") (pintype "bidirectional"))
    )
    (net (code "65") (name "Net-(U1B-PB1)") (class "Default")
      (node (ref "J8") (pin "6") (pinfunction "6_6") (pintype "passive"))
      (node (ref "U1") (pin "CN10_24") (pinfunction "PB1_CN10_24") (pintype "bidirectional"))
    )
    (net (code "66") (name "Net-(U1B-PB6)") (class "Default")
      (node (ref "J5") (pin "4") (pinfunction "4_4") (pintype "passive"))
      (node (ref "U1") (pin "CN10_17") (pinfunction "PB6_CN10_17") (pintype "bidirectional"))
    )
    (net (code "67") (name "Net-(U1B-PB10)") (class "Default")
      (node (ref "J8") (pin "5") (pinfunction "5_5") (pintype "passive"))
      (node (ref "U1") (pin "CN10_25") (pinfunction "PB10_CN10_25") (pintype "bidirectional"))
    )
    (net (code "68") (name "Net-(U1B-PB15)") (class "Default")
      (node (ref "J8") (pin "4") (pinfunction "4_4") (pintype "passive"))
      (node (ref "U1") (pin "CN10_26") (pinfunction "PB15_CN10_26") (pintype "bidirectional"))
    )
    (net (code "69") (name "Net-(U1B-PC4)") (class "Default")
      (node (ref "U1") (pin "CN10_34") (pinfunction "PC4_CN10_34") (pintype "bidirectional"))
      (node (ref "U4") (pin "4") (pinfunction "OUTPUT_B_4") (pintype "bidirectional"))
    )
    (net (code "70") (name "Net-(U1B-PC6)") (class "Default")
      (node (ref "J11") (pin "3") (pinfunction "3_3") (pintype "passive"))
      (node (ref "R29") (pin "1") (pinfunction "1_1") (pintype "passive"))
      (node (ref "U1") (pin "CN10_4") (pinfunction "PC6_CN10_4") (pintype "bidirectional"))
    )
    (net (code "71") (name "Net-(U1B-PC7)") (class "Default")
      (node (ref "J11") (pin "1") (pinfunction "1_1") (pintype "passive"))
      (node (ref "R30") (pin "1") (pinfunction "1_1") (pintype "passive"))
      (node (ref "U1") (pin "CN10_19") (pinfunction "PC7_CN10_19") (pintype "bidirectional"))
    )
    (net (code "72") (name "Net-(U1B-PC9)") (class "Default")
      (node (ref "J10") (pin "1") (pinfunction "1_1") (pintype "passive"))
      (node (ref "R28") (pin "1") (pinfunction "1_1") (pintype "passive"))
      (node (ref "U1") (pin "CN10_1") (pinfunction "PC9_CN10_1") (pintype "bidirectional"))
    )
    (net (code "73") (name "Net-(U2--INC)") (class "Default")
      (node (ref "J9") (pin "4") (pinfunction "4_4") (pintype "bidirectional"))
      (node (ref "U2") (pin "8") (pinfunction "OUTC_8") (pintype "output"))
      (node (ref "U2") (pin "9") (pinfunction "-INC_9") (pintype "input"))
    )
    (net (code "74") (name "Net-(U2--IND)") (class "Default")
      (node (ref "J9") (pin "3") (pinfunction "3_3") (pintype "bidirectional"))
      (node (ref "U2") (pin "13") (pinfunction "-IND_13") (pintype "input"))
      (node (ref "U2") (pin "14") (pinfunction "OUTD_14") (pintype "output"))
    )
    (net (code "75") (name "Net-(U3--INC)") (class "Default")
      (node (ref "J7") (pin "4") (pinfunction "4_4") (pintype "bidirectional"))
      (node (ref "U3") (pin "8") (pinfunction "OUTC_8") (pintype "output"))
      (node (ref "U3") (pin "9") (pinfunction "-INC_9") (pintype "input"))
    )
    (net (code "76") (name "Net-(U3--IND)") (class "Default")
      (node (ref "J7") (pin "3") (pinfunction "3_3") (pintype "bidirectional"))
      (node (ref "U3") (pin "13") (pinfunction "-IND_13") (pintype "input"))
      (node (ref "U3") (pin "14") (pinfunction "OUTD_14") (pintype "output"))
    )
    (net (code "77") (name "Net-(U6-B1)") (class "Default")
      (node (ref "J23") (pin "1") (pinfunction "1_1") (pintype "passive"))
      (node (ref "U6") (pin "3") (pinfunction "B1_3") (pintype "bidirectional"))
    )
    (net (code "78") (name "Net-(U6-B2)") (class "Default")
      (node (ref "J23") (pin "2") (pinfunction "2_2") (pintype "passive"))
      (node (ref "U6") (pin "6") (pinfunction "B2_6") (pintype "bidirectional"))
    )
    (net (code "79") (name "Net-(U6-B3)") (class "Default")
      (node (ref "J23") (pin "3") (pinfunction "3_3") (pintype "passive"))
      (node (ref "U6") (pin "10") (pinfunction "B3_10") (pintype "bidirectional"))
    )
    (net (code "80") (name "Net-(U6-Y1)") (class "Default")
      (node (ref "R7") (pin "1") (pinfunction "1_1") (pintype "passive"))
      (node (ref "U6") (pin "4") (pinfunction "Y1_4") (pintype "bidirectional"))
    )
    (net (code "81") (name "Net-(U6-Y2)") (class "Default")
      (node (ref "R10") (pin "1") (pinfunction "1_1") (pintype "passive"))
      (node (ref "U6") (pin "7") (pinfunction "Y2_7") (pintype "bidirectional"))
    )
    (net (code "82") (name "Net-(U6-Y3)") (class "Default")
      (node (ref "R8") (pin "1") (pinfunction "1_1") (pintype "passive"))
      (node (ref "U6") (pin "9") (pinfunction "Y3_9") (pintype "bidirectional"))
    )
    (net (code "83") (name "Net-(U7-B1)") (class "Default")
      (node (ref "J23") (pin "5") (pinfunction "5_5") (pintype "passive"))
      (node (ref "U7") (pin "3") (pinfunction "B1_3") (pintype "bidirectional"))
    )
    (net (code "84") (name "Net-(U7-B2)") (class "Default")
      (node (ref "J23") (pin "6") (pinfunction "6_6") (pintype "passive"))
      (node (ref "U7") (pin "6") (pinfunction "B2_6") (pintype "bidirectional"))
    )
    (net (code "85") (name "Net-(U7-B3)") (class "Default")
      (node (ref "J23") (pin "7") (pinfunction "7_7") (pintype "passive"))
      (node (ref "U7") (pin "10") (pinfunction "B3_10") (pintype "bidirectional"))
    )
    (net (code "86") (name "Net-(U7-Y1)") (class "Default")
      (node (ref "R11") (pin "1") (pinfunction "1_1") (pintype "passive"))
      (node (ref "U7") (pin "4") (pinfunction "Y1_4") (pintype "bidirectional"))
    )
    (net (code "87") (name "Net-(U7-Y2)") (class "Default")
      (node (ref "R12") (pin "1") (pinfunction "1_1") (pintype "passive"))
      (node (ref "U7") (pin "7") (pinfunction "Y2_7") (pintype "bidirectional"))
    )
    (net (code "88") (name "Net-(U7-Y3)") (class "Default")
      (node (ref "R14") (pin "1") (pinfunction "1_1") (pintype "passive"))
      (node (ref "U7") (pin "9") (pinfunction "Y3_9") (pintype "bidirectional"))
    )
    (net (code "89") (name "unconnected-(IC3-1A-Pad1)") (class "Default")
      (node (ref "IC3") (pin "1") (pinfunction "1A_1") (pintype "bidirectional"))
    )
    (net (code "90") (name "unconnected-(IC3-1Y-Pad2)") (class "Default")
      (node (ref "IC3") (pin "2") (pinfunction "1Y_2") (pintype "bidirectional"))
    )
    (net (code "91") (name "unconnected-(IC3-2A-Pad3)") (class "Default")
      (node (ref "IC3") (pin "3") (pinfunction "2A_3") (pintype "bidirectional"))
    )
    (net (code "92") (name "unconnected-(IC3-2Y-Pad4)") (class "Default")
      (node (ref "IC3") (pin "4") (pinfunction "2Y_4") (pintype "bidirectional"))
    )
    (net (code "93") (name "unconnected-(IC3-3A-Pad5)") (class "Default")
      (node (ref "IC3") (pin "5") (pinfunction "3A_5") (pintype "bidirectional"))
    )
    (net (code "94") (name "unconnected-(IC3-3Y-Pad6)") (class "Default")
      (node (ref "IC3") (pin "6") (pinfunction "3Y_6") (pintype "bidirectional"))
    )
    (net (code "95") (name "unconnected-(IC3-5A-Pad11)") (class "Default")
      (node (ref "IC3") (pin "11") (pinfunction "5A_11") (pintype "bidirectional"))
    )
    (net (code "96") (name "unconnected-(IC3-5Y-Pad10)") (class "Default")
      (node (ref "IC3") (pin "10") (pinfunction "5Y_10") (pintype "bidirectional"))
    )
    (net (code "97") (name "unconnected-(IC4-N{slash}C_1-Pad1)") (class "Default")
      (node (ref "IC4") (pin "1") (pinfunction "N/C_1_1") (pintype "bidirectional"))
    )
    (net (code "98") (name "unconnected-(IC4-N{slash}C_2-Pad5)") (class "Default")
      (node (ref "IC4") (pin "5") (pinfunction "N/C_2_5") (pintype "bidirectional"))
    )
    (net (code "99") (name "unconnected-(IC4-N{slash}C_3-Pad8)") (class "Default")
      (node (ref "IC4") (pin "8") (pinfunction "N/C_3_8") (pintype "bidirectional"))
    )
    (net (code "100") (name "unconnected-(IC5-N{slash}C_1-Pad1)") (class "Default")
      (node (ref "IC5") (pin "1") (pinfunction "N/C_1_1") (pintype "bidirectional"))
    )
    (net (code "101") (name "unconnected-(IC5-N{slash}C_2-Pad5)") (class "Default")
      (node (ref "IC5") (pin "5") (pinfunction "N/C_2_5") (pintype "bidirectional"))
    )
    (net (code "102") (name "unconnected-(IC5-N{slash}C_3-Pad8)") (class "Default")
      (node (ref "IC5") (pin "8") (pinfunction "N/C_3_8") (pintype "bidirectional"))
    )
    (net (code "103") (name "unconnected-(J1-Pad1)") (class "Default")
      (node (ref "J1") (pin "1") (pinfunction "1_1") (pintype "passive"))
    )
    (net (code "104") (name "unconnected-(J15-Pad1)") (class "Default")
      (node (ref "J15") (pin "1") (pinfunction "1_1") (pintype "passive"))
    )
    (net (code "105") (name "unconnected-(U1-PadCN11_1)") (class "Default")
      (node (ref "U1") (pin "CN11_1") (pinfunction "CN11_1_CN11_1") (pintype "passive"))
    )
    (net (code "106") (name "unconnected-(U1-PadCN11_2)") (class "Default")
      (node (ref "U1") (pin "CN11_2") (pinfunction "CN11_2_CN11_2") (pintype "passive"))
    )
    (net (code "107") (name "unconnected-(U1-PadCN12_1)") (class "Default")
      (node (ref "U1") (pin "CN12_1") (pinfunction "CN12_1_CN12_1") (pintype "passive"))
    )
    (net (code "108") (name "unconnected-(U1-PadCN12_2)") (class "Default")
      (node (ref "U1") (pin "CN12_2") (pinfunction "CN12_2_CN12_2") (pintype "passive"))
    )
    (net (code "109") (name "unconnected-(U1A-BOOT0-PadCN7_7)") (class "Default")
      (node (ref "U1") (pin "CN7_7") (pinfunction "BOOT0_CN7_7") (pintype "bidirectional"))
    )
    (net (code "110") (name "unconnected-(U1A-IOREF-PadCN7_12)") (class "Default")
      (node (ref "U1") (pin "CN7_12") (pinfunction "IOREF_CN7_12") (pintype "bidirectional"))
    )
    (net (code "111") (name "unconnected-(U1A-NC_9-PadCN7_9)") (class "Default")
      (node (ref "U1") (pin "CN7_9") (pinfunction "NC_9_CN7_9") (pintype "no_connect"))
    )
    (net (code "112") (name "unconnected-(U1A-NC_10_CN7-PadCN7_10)") (class "Default")
      (node (ref "U1") (pin "CN7_10") (pinfunction "NC_10_CN7_CN7_10") (pintype "no_connect"))
    )
    (net (code "113") (name "unconnected-(U1A-NC_11-PadCN7_11)") (class "Default")
      (node (ref "U1") (pin "CN7_11") (pinfunction "NC_11_CN7_11") (pintype "no_connect"))
    )
    (net (code "114") (name "unconnected-(U1A-NC_26-PadCN7_26)") (class "Default")
      (node (ref "U1") (pin "CN7_26") (pinfunction "NC_26_CN7_26") (pintype "no_connect"))
    )
    (net (code "115") (name "unconnected-(U1A-PA13-PadCN7_13)") (class "Default")
      (node (ref "U1") (pin "CN7_13") (pinfunction "PA13_CN7_13") (pintype "bidirectional"))
    )
    (net (code "116") (name "unconnected-(U1A-PA14-PadCN7_15)") (class "Default")
      (node (ref "U1") (pin "CN7_15") (pinfunction "PA14_CN7_15") (pintype "bidirectional"))
    )
    (net (code "117") (name "unconnected-(U1A-PA15-PadCN7_17)") (class "Default")
      (node (ref "U1") (pin "CN7_17") (pinfunction "PA15_CN7_17") (pintype "bidirectional"))
    )
    (net (code "118") (name "unconnected-(U1A-PC14-PadCN7_25)") (class "Default")
      (node (ref "U1") (pin "CN7_25") (pinfunction "PC14_CN7_25") (pintype "bidirectional"))
    )
    (net (code "119") (name "unconnected-(U1A-PC15-PadCN7_27)") (class "Default")
      (node (ref "U1") (pin "CN7_27") (pinfunction "PC15_CN7_27") (pintype "bidirectional"))
    )
    (net (code "120") (name "unconnected-(U1A-PD2-PadCN7_4)") (class "Default")
      (node (ref "U1") (pin "CN7_4") (pinfunction "PD2_CN7_4") (pintype "bidirectional"))
    )
    (net (code "121") (name "unconnected-(U1A-PH0-PadCN7_29)") (class "Default")
      (node (ref "U1") (pin "CN7_29") (pinfunction "PH0_CN7_29") (pintype "bidirectional"))
    )
    (net (code "122") (name "unconnected-(U1A-PH1-PadCN7_31)") (class "Default")
      (node (ref "U1") (pin "CN7_31") (pinfunction "PH1_CN7_31") (pintype "bidirectional"))
    )
    (net (code "123") (name "unconnected-(U1A-RESET-PadCN7_14)") (class "Default")
      (node (ref "U1") (pin "CN7_14") (pinfunction "RESET_CN7_14") (pintype "bidirectional"))
    )
    (net (code "124") (name "unconnected-(U1A-VIN-PadCN7_24)") (class "Default")
      (node (ref "U1") (pin "CN7_24") (pinfunction "VIN_CN7_24") (pintype "bidirectional"))
    )
    (net (code "125") (name "unconnected-(U1B-NC_10_CN10-PadCN10_10)") (class "Default")
      (node (ref "U1") (pin "CN10_10") (pinfunction "NC_10_CN10_CN10_10") (pintype "no_connect"))
    )
    (net (code "126") (name "unconnected-(U1B-NC_18-PadCN10_18)") (class "Default")
      (node (ref "U1") (pin "CN10_18") (pinfunction "NC_18_CN10_18") (pintype "no_connect"))
    )
    (net (code "127") (name "unconnected-(U1B-NC_36-PadCN10_36)") (class "Default")
      (node (ref "U1") (pin "CN10_36") (pinfunction "NC_36_CN10_36") (pintype "no_connect"))
    )
    (net (code "128") (name "unconnected-(U1B-NC_38-PadCN10_38)") (class "Default")
      (node (ref "U1") (pin "CN10_38") (pinfunction "NC_38_CN10_38") (pintype "no_connect"))
    )
    (net (code "129") (name "unconnected-(U1B-PA2-PadCN10_35)") (class "Default")
      (node (ref "U1") (pin "CN10_35") (pinfunction "PA2_CN10_35") (pintype "bidirectional"))
    )
    (net (code "130") (name "unconnected-(U1B-PA3-PadCN10_37)") (class "Default")
      (node (ref "U1") (pin "CN10_37") (pinfunction "PA3_CN10_37") (pintype "bidirectional"))
    )
    (net (code "131") (name "unconnected-(U1B-PA5-PadCN10_11)") (class "Default")
      (node (ref "U1") (pin "CN10_11") (pinfunction "PA5_CN10_11") (pintype "bidirectional"))
    )
    (net (code "132") (name "unconnected-(U1B-PA9-PadCN10_21)") (class "Default")
      (node (ref "U1") (pin "CN10_21") (pinfunction "PA9_CN10_21") (pintype "bidirectional"))
    )
    (net (code "133") (name "unconnected-(U1B-PA10-PadCN10_33)") (class "Default")
      (node (ref "U1") (pin "CN10_33") (pinfunction "PA10_CN10_33") (pintype "bidirectional"))
    )
    (net (code "134") (name "unconnected-(U1B-PA11-PadCN10_14)") (class "Default")
      (node (ref "U1") (pin "CN10_14") (pinfunction "PA11_CN10_14") (pintype "bidirectional"))
    )
    (net (code "135") (name "unconnected-(U1B-PB8-PadCN10_3)") (class "Default")
      (node (ref "U1") (pin "CN10_3") (pinfunction "PB8_CN10_3") (pintype "bidirectional"))
    )
    (net (code "136") (name "unconnected-(U1B-PB9-PadCN10_5)") (class "Default")
      (node (ref "U1") (pin "CN10_5") (pinfunction "PB9_CN10_5") (pintype "bidirectional"))
    )
    (net (code "137") (name "unconnected-(U1B-PB12-PadCN10_16)") (class "Default")
      (node (ref "U1") (pin "CN10_16") (pinfunction "PB12_CN10_16") (pintype "bidirectional"))
    )
    (net (code "138") (name "unconnected-(U1B-PB13-PadCN10_30)") (class "Default")
      (node (ref "U1") (pin "CN10_30") (pinfunction "PB13_CN10_30") (pintype "bidirectional"))
    )
    (net (code "139") (name "unconnected-(U1B-PB14-PadCN10_28)") (class "Default")
      (node (ref "U1") (pin "CN10_28") (pinfunction "PB14_CN10_28") (pintype "bidirectional"))
    )
    (net (code "140") (name "unconnected-(U1B-PC8-PadCN10_2)") (class "Default")
      (node (ref "U1") (pin "CN10_2") (pinfunction "PC8_CN10_2") (pintype "bidirectional"))
    )
    (net (code "141") (name "unconnected-(U2-+INA_-Pad3)") (class "Default")
      (node (ref "U2") (pin "3") (pinfunction "+INA__3") (pintype "input"))
    )
    (net (code "142") (name "unconnected-(U2-+INB-Pad5)") (class "Default")
      (node (ref "U2") (pin "5") (pinfunction "+INB_5") (pintype "input"))
    )
    (net (code "143") (name "unconnected-(U2--INA-Pad2)") (class "Default")
      (node (ref "U2") (pin "2") (pinfunction "-INA_2") (pintype "input"))
    )
    (net (code "144") (name "unconnected-(U2--INB-Pad6)") (class "Default")
      (node (ref "U2") (pin "6") (pinfunction "-INB_6") (pintype "input"))
    )
    (net (code "145") (name "unconnected-(U2-OUTA-Pad1)") (class "Default")
      (node (ref "U2") (pin "1") (pinfunction "OUTA_1") (pintype "output"))
    )
    (net (code "146") (name "unconnected-(U2-OUTB-Pad7)") (class "Default")
      (node (ref "U2") (pin "7") (pinfunction "OUTB_7") (pintype "output"))
    )
    (net (code "147") (name "unconnected-(U3-+INA_-Pad3)") (class "Default")
      (node (ref "U3") (pin "3") (pinfunction "+INA__3") (pintype "input"))
    )
    (net (code "148") (name "unconnected-(U3-+INB-Pad5)") (class "Default")
      (node (ref "U3") (pin "5") (pinfunction "+INB_5") (pintype "input"))
    )
    (net (code "149") (name "unconnected-(U3--INA-Pad2)") (class "Default")
      (node (ref "U3") (pin "2") (pinfunction "-INA_2") (pintype "input"))
    )
    (net (code "150") (name "unconnected-(U3--INB-Pad6)") (class "Default")
      (node (ref "U3") (pin "6") (pinfunction "-INB_6") (pintype "input"))
    )
    (net (code "151") (name "unconnected-(U3-OUTA-Pad1)") (class "Default")
      (node (ref "U3") (pin "1") (pinfunction "OUTA_1") (pintype "output"))
    )
    (net (code "152") (name "unconnected-(U3-OUTB-Pad7)") (class "Default")
      (node (ref "U3") (pin "7") (pinfunction "OUTB_7") (pintype "output"))
    )
    (net (code "153") (name "unconnected-(U6-A4-Pad14)") (class "Default")
      (node (ref "U6") (pin "14") (pinfunction "A4_14") (pintype "bidirectional"))
    )
    (net (code "154") (name "unconnected-(U6-B4-Pad13)") (class "Default")
      (node (ref "U6") (pin "13") (pinfunction "B4_13") (pintype "bidirectional"))
    )
    (net (code "155") (name "unconnected-(U6-Y4-Pad12)") (class "Default")
      (node (ref "U6") (pin "12") (pinfunction "Y4_12") (pintype "bidirectional"))
    )
    (net (code "156") (name "unconnected-(U7-A4-Pad14)") (class "Default")
      (node (ref "U7") (pin "14") (pinfunction "A4_14") (pintype "bidirectional"))
    )
    (net (code "157") (name "unconnected-(U7-B4-Pad13)") (class "Default")
      (node (ref "U7") (pin "13") (pinfunction "B4_13") (pintype "bidirectional"))
    )
    (net (code "158") (name "unconnected-(U7-Y4-Pad12)") (class "Default")
      (node (ref "U7") (pin "12") (pinfunction "Y4_12") (pintype "bidirectional"))
    )
  )
)
